# anemix.net
KiCad netlist of a schematic drawn in EAGLE
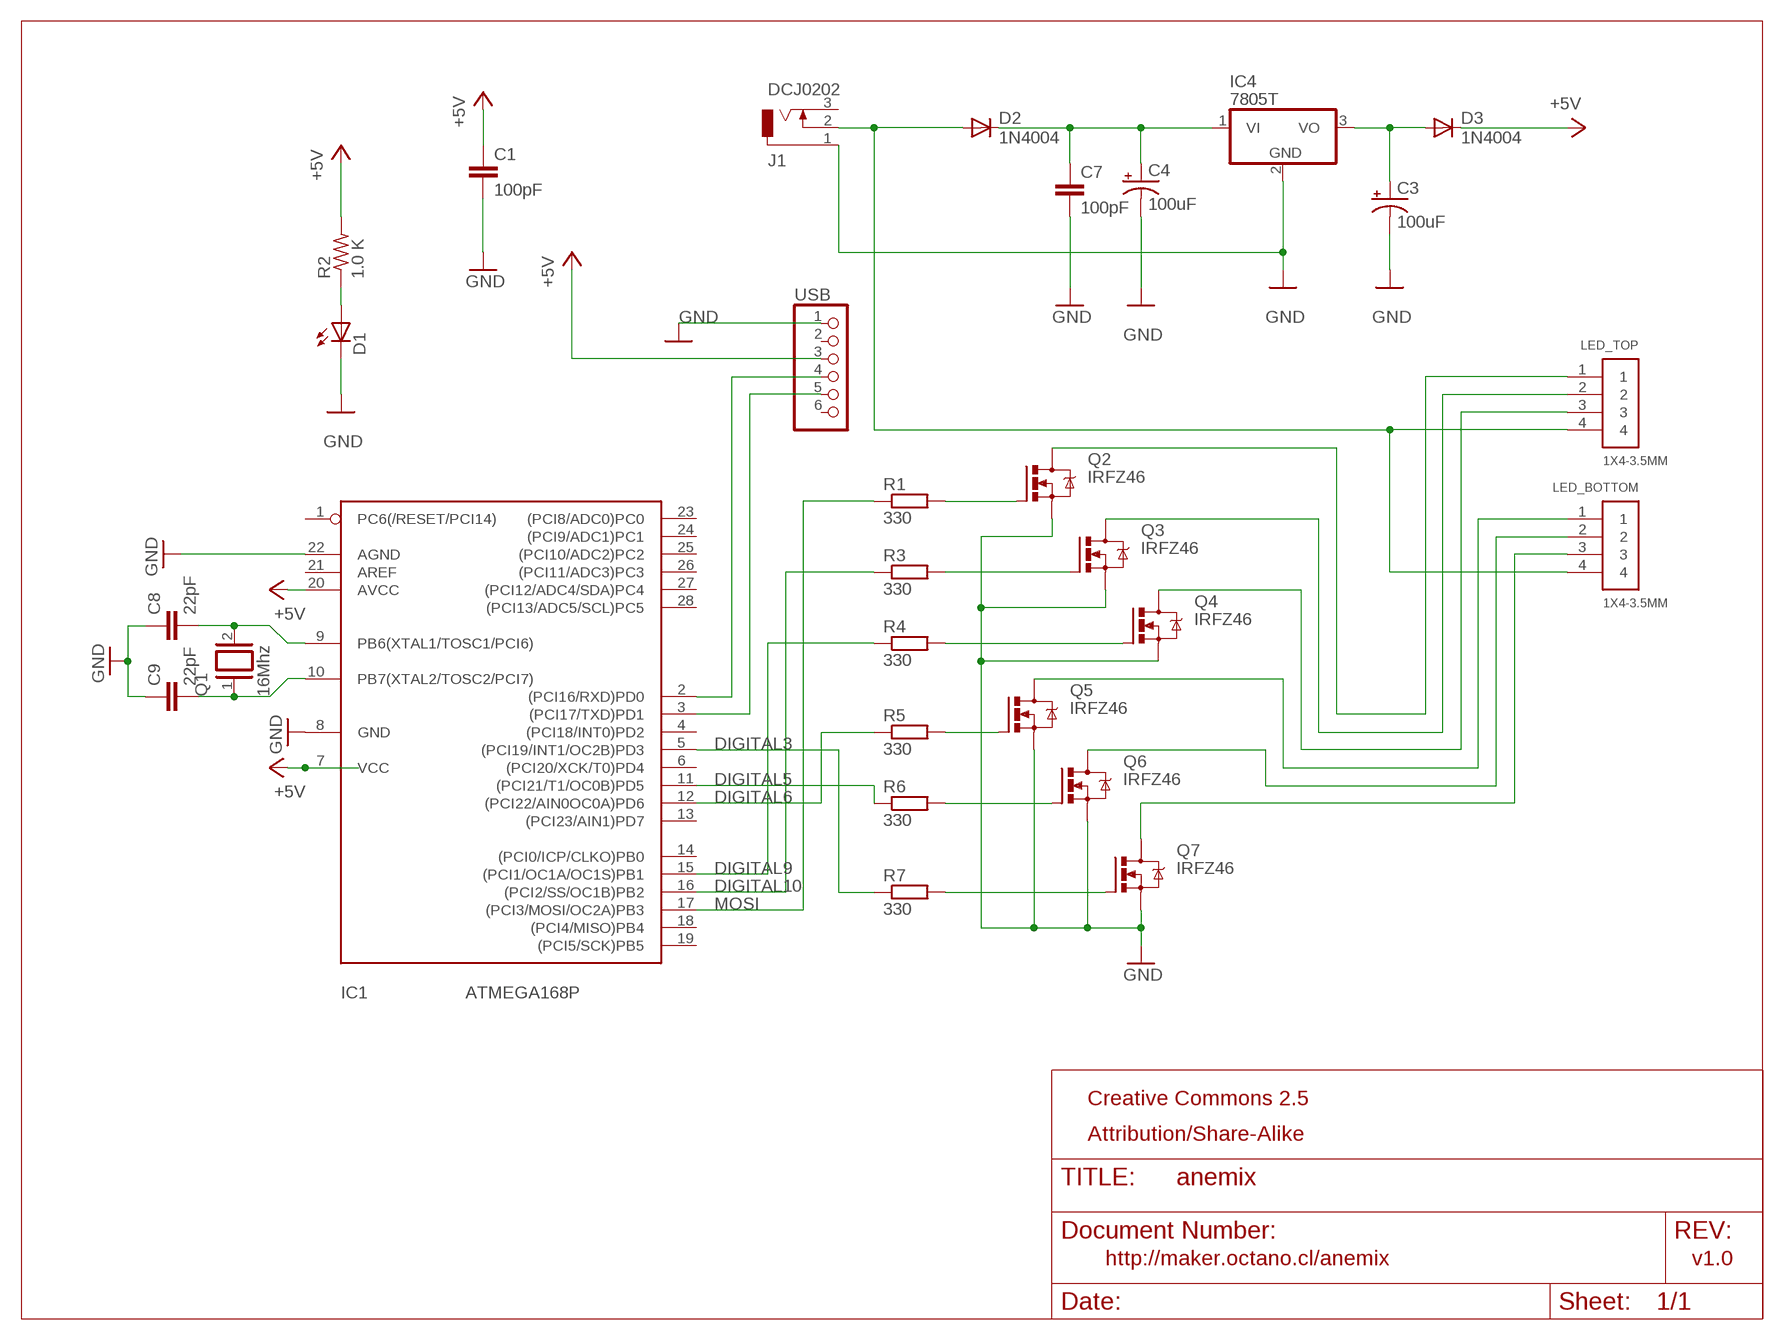
[diagram p0: schematic, sheet 1]

(export (version "E")
  (design (tool "Eeschema 10.0.6"))
  (components
    (comp (ref "C1")
      (value "100pF")
      (footprint "eagle-import:C025-025X050")
      (libsource (lib "eagle-import") (part "C-EU025-025X050"))
    )
    (comp (ref "C3")
      (value "100uF")
      (footprint "eagle-import:E2,5-7")
      (libsource (lib "eagle-import") (part "CPOL-USE2.5-7"))
    )
    (comp (ref "C4")
      (value "100uF")
      (footprint "eagle-import:E2,5-7")
      (libsource (lib "eagle-import") (part "CPOL-USE2.5-7"))
    )
    (comp (ref "C7")
      (value "100pF")
      (footprint "eagle-import:C025-025X050")
      (libsource (lib "eagle-import") (part "C-EU025-025X050"))
    )
    (comp (ref "C8")
      (value "22pF")
      (footprint "eagle-import:C025-025X050")
      (libsource (lib "eagle-import") (part "C-EU025-025X050"))
    )
    (comp (ref "C9")
      (value "22pF")
      (footprint "eagle-import:C025-025X050")
      (libsource (lib "eagle-import") (part "C-EU025-025X050"))
    )
    (comp (ref "D1")
      (value "LED3MM")
      (footprint "eagle-import:LED3MM")
      (libsource (lib "eagle-import") (part "LED3MM"))
    )
    (comp (ref "D2")
      (value "1N4004")
      (footprint "eagle-import:DO41-10")
      (libsource (lib "eagle-import") (part "1N4004"))
    )
    (comp (ref "D3")
      (value "1N4004")
      (footprint "eagle-import:DO41-10")
      (libsource (lib "eagle-import") (part "1N4004"))
    )
    (comp (ref "IC1")
      (value "ATMEGA168P")
      (footprint "eagle-import:DIL28_3")
      (libsource (lib "eagle-import") (part "ATMEGA168PROUND"))
    )
    (comp (ref "IC4")
      (value "7805T")
      (footprint "eagle-import:TO220H")
      (libsource (lib "eagle-import") (part "78T05"))
    )
    (comp (ref "J1")
      (value "DCJ0202")
      (footprint "eagle-import:DCJ0202")
      (libsource (lib "eagle-import") (part "DCJ0202"))
    )
    (comp (ref "LED_BOTTOM")
      (value "1X4-3.5MM")
      (footprint "eagle-import:1X04-3.5MM")
      (libsource (lib "eagle-import") (part "1X4-3.5MM"))
    )
    (comp (ref "LED_TOP")
      (value "1X4-3.5MM")
      (footprint "eagle-import:1X04-3.5MM")
      (libsource (lib "eagle-import") (part "1X4-3.5MM"))
    )
    (comp (ref "Q1")
      (value "16Mhz")
      (footprint "eagle-import:QS")
      (libsource (lib "eagle-import") (part "XTAL/S"))
    )
    (comp (ref "Q2")
      (value "IRFZ46")
      (footprint "eagle-import:TO220BH")
      (libsource (lib "eagle-import") (part "IRFZ48Z"))
    )
    (comp (ref "Q3")
      (value "IRFZ46")
      (footprint "eagle-import:TO220BH")
      (libsource (lib "eagle-import") (part "IRFZ48Z"))
    )
    (comp (ref "Q4")
      (value "IRFZ46")
      (footprint "eagle-import:TO220BH")
      (libsource (lib "eagle-import") (part "IRFZ48Z"))
    )
    (comp (ref "Q5")
      (value "IRFZ46")
      (footprint "eagle-import:TO220BH")
      (libsource (lib "eagle-import") (part "IRFZ48Z"))
    )
    (comp (ref "Q6")
      (value "IRFZ46")
      (footprint "eagle-import:TO220BH")
      (libsource (lib "eagle-import") (part "IRFZ48Z"))
    )
    (comp (ref "Q7")
      (value "IRFZ46")
      (footprint "eagle-import:TO220BH")
      (libsource (lib "eagle-import") (part "IRFZ48Z"))
    )
    (comp (ref "R1")
      (value "330")
      (footprint "eagle-import:0207_10")
      (libsource (lib "eagle-import") (part "R-EU_0207/10"))
    )
    (comp (ref "R2")
      (value "1.0 K")
      (footprint "eagle-import:0204_7")
      (libsource (lib "eagle-import") (part "R-US_0204/7"))
    )
    (comp (ref "R3")
      (value "330")
      (footprint "eagle-import:0207_10")
      (libsource (lib "eagle-import") (part "R-EU_0207/10"))
    )
    (comp (ref "R4")
      (value "330")
      (footprint "eagle-import:0207_10")
      (libsource (lib "eagle-import") (part "R-EU_0207/10"))
    )
    (comp (ref "R5")
      (value "330")
      (footprint "eagle-import:0207_10")
      (libsource (lib "eagle-import") (part "R-EU_0207/10"))
    )
    (comp (ref "R6")
      (value "330")
      (footprint "eagle-import:0207_10")
      (libsource (lib "eagle-import") (part "R-EU_0207/10"))
    )
    (comp (ref "R7")
      (value "330")
      (footprint "eagle-import:0207_10")
      (libsource (lib "eagle-import") (part "R-EU_0207/10"))
    )
    (comp (ref "USB")
      (value "PINHD-1X6")
      (footprint "eagle-import:1X06")
      (libsource (lib "eagle-import") (part "PINHD-1X6"))
    )
  )
  (nets
    (net (code "1") (name "+5V") (class "Default")
      (node (ref "C1") (pin "1") (pinfunction "1_1") (pintype "passive"))
      (node (ref "D3") (pin "C") (pinfunction "C_C") (pintype "passive"))
      (node (ref "IC1") (pin "20") (pinfunction "AVCC_20") (pintype "bidirectional"))
      (node (ref "IC1") (pin "7") (pinfunction "VCC_7") (pintype "bidirectional"))
      (node (ref "R2") (pin "2") (pinfunction "2_2") (pintype "passive"))
      (node (ref "USB") (pin "3") (pinfunction "3_3") (pintype "passive"))
    )
    (net (code "2") (name "/DIGITAL3") (class "Default")
      (node (ref "IC1") (pin "5") (pinfunction "(PCI19/INT1/OC2B)PD3_5") (pintype "bidirectional"))
      (node (ref "R7") (pin "1") (pinfunction "1_1") (pintype "passive"))
    )
    (net (code "3") (name "/DIGITAL5") (class "Default")
      (node (ref "IC1") (pin "11") (pinfunction "(PCI21/T1/OC0B)PD5_11") (pintype "bidirectional"))
      (node (ref "R6") (pin "1") (pinfunction "1_1") (pintype "passive"))
    )
    (net (code "4") (name "/DIGITAL6") (class "Default")
      (node (ref "IC1") (pin "12") (pinfunction "(PCI22/AIN0OC0A)PD6_12") (pintype "bidirectional"))
      (node (ref "R5") (pin "1") (pinfunction "1_1") (pintype "passive"))
    )
    (net (code "5") (name "/DIGITAL9") (class "Default")
      (node (ref "IC1") (pin "15") (pinfunction "(PCI1/OC1A/OC1S)PB1_15") (pintype "bidirectional"))
      (node (ref "R4") (pin "1") (pinfunction "1_1") (pintype "passive"))
    )
    (net (code "6") (name "/DIGITAL10") (class "Default")
      (node (ref "IC1") (pin "16") (pinfunction "(PCI2/SS/OC1B)PB2_16") (pintype "bidirectional"))
      (node (ref "R3") (pin "1") (pinfunction "1_1") (pintype "passive"))
    )
    (net (code "7") (name "/MOSI") (class "Default")
      (node (ref "IC1") (pin "17") (pinfunction "(PCI3/MOSI/OC2A)PB3_17") (pintype "bidirectional"))
      (node (ref "R1") (pin "1") (pinfunction "1_1") (pintype "passive"))
    )
    (net (code "8") (name "GND") (class "Default")
      (node (ref "C1") (pin "2") (pinfunction "2_2") (pintype "passive"))
      (node (ref "C3") (pin "-") (pinfunction "-_-") (pintype "passive"))
      (node (ref "C4") (pin "-") (pinfunction "-_-") (pintype "passive"))
      (node (ref "C7") (pin "2") (pinfunction "2_2") (pintype "passive"))
      (node (ref "C8") (pin "1") (pinfunction "1_1") (pintype "passive"))
      (node (ref "C9") (pin "1") (pinfunction "1_1") (pintype "passive"))
      (node (ref "D1") (pin "K") (pinfunction "C_K") (pintype "passive"))
      (node (ref "IC1") (pin "22") (pinfunction "AGND_22") (pintype "bidirectional"))
      (node (ref "IC1") (pin "8") (pinfunction "GND_8") (pintype "bidirectional"))
      (node (ref "IC4") (pin "2") (pinfunction "GND_2") (pintype "passive"))
      (node (ref "J1") (pin "1") (pinfunction "1_1") (pintype "passive"))
      (node (ref "Q2") (pin "S") (pinfunction "S_S") (pintype "passive"))
      (node (ref "Q3") (pin "S") (pinfunction "S_S") (pintype "passive"))
      (node (ref "Q4") (pin "S") (pinfunction "S_S") (pintype "passive"))
      (node (ref "Q5") (pin "S") (pinfunction "S_S") (pintype "passive"))
      (node (ref "Q6") (pin "S") (pinfunction "S_S") (pintype "passive"))
      (node (ref "Q7") (pin "S") (pinfunction "S_S") (pintype "passive"))
      (node (ref "USB") (pin "1") (pinfunction "1_1") (pintype "passive"))
    )
    (net (code "9") (name "Net-(D1-PadA)") (class "Default")
      (node (ref "D1") (pin "A") (pinfunction "A_A") (pintype "passive"))
      (node (ref "R2") (pin "1") (pinfunction "1_1") (pintype "passive"))
    )
    (net (code "10") (name "Net-(D2-PadA)") (class "Default")
      (node (ref "D2") (pin "A") (pinfunction "A_A") (pintype "passive"))
      (node (ref "J1") (pin "2") (pinfunction "2_2") (pintype "passive"))
      (node (ref "LED_BOTTOM") (pin "4") (pinfunction "4_4") (pintype "bidirectional"))
      (node (ref "LED_TOP") (pin "4") (pinfunction "4_4") (pintype "bidirectional"))
    )
    (net (code "11") (name "Net-(IC1-(PCI16{slash}RXD)PD0)") (class "Default")
      (node (ref "IC1") (pin "2") (pinfunction "(PCI16/RXD)PD0_2") (pintype "bidirectional"))
      (node (ref "USB") (pin "4") (pinfunction "4_4") (pintype "passive"))
    )
    (net (code "12") (name "Net-(IC1-(PCI17{slash}TXD)PD1)") (class "Default")
      (node (ref "IC1") (pin "3") (pinfunction "(PCI17/TXD)PD1_3") (pintype "bidirectional"))
      (node (ref "USB") (pin "5") (pinfunction "5_5") (pintype "passive"))
    )
    (net (code "13") (name "Net-(IC1-PB6(XTAL1{slash}TOSC1{slash}PCI6))") (class "Default")
      (node (ref "C8") (pin "2") (pinfunction "2_2") (pintype "passive"))
      (node (ref "IC1") (pin "9") (pinfunction "PB6(XTAL1/TOSC1/PCI6)_9") (pintype "bidirectional"))
      (node (ref "Q1") (pin "2") (pinfunction "2_2") (pintype "passive"))
    )
    (net (code "14") (name "Net-(IC1-PB7(XTAL2{slash}TOSC2{slash}PCI7))") (class "Default")
      (node (ref "C9") (pin "2") (pinfunction "2_2") (pintype "passive"))
      (node (ref "IC1") (pin "10") (pinfunction "PB7(XTAL2/TOSC2/PCI7)_10") (pintype "bidirectional"))
      (node (ref "Q1") (pin "1") (pinfunction "1_1") (pintype "passive"))
    )
    (net (code "15") (name "Net-(IC4-VI)") (class "Default")
      (node (ref "C4") (pin "+") (pinfunction "+_+") (pintype "passive"))
      (node (ref "C7") (pin "1") (pinfunction "1_1") (pintype "passive"))
      (node (ref "D2") (pin "C") (pinfunction "C_C") (pintype "passive"))
      (node (ref "IC4") (pin "1") (pinfunction "VI_1") (pintype "input"))
    )
    (net (code "16") (name "Net-(IC4-VO)") (class "Default")
      (node (ref "C3") (pin "+") (pinfunction "+_+") (pintype "passive"))
      (node (ref "D3") (pin "A") (pinfunction "A_A") (pintype "passive"))
      (node (ref "IC4") (pin "3") (pinfunction "VO_3") (pintype "passive"))
    )
    (net (code "17") (name "Net-(LED_BOTTOM-Pad1)") (class "Default")
      (node (ref "LED_BOTTOM") (pin "1") (pinfunction "1_1") (pintype "bidirectional"))
      (node (ref "Q5") (pin "D") (pinfunction "D_D") (pintype "passive"))
    )
    (net (code "18") (name "Net-(LED_BOTTOM-Pad2)") (class "Default")
      (node (ref "LED_BOTTOM") (pin "2") (pinfunction "2_2") (pintype "bidirectional"))
      (node (ref "Q6") (pin "D") (pinfunction "D_D") (pintype "passive"))
    )
    (net (code "19") (name "Net-(LED_BOTTOM-Pad3)") (class "Default")
      (node (ref "LED_BOTTOM") (pin "3") (pinfunction "3_3") (pintype "bidirectional"))
      (node (ref "Q7") (pin "D") (pinfunction "D_D") (pintype "passive"))
    )
    (net (code "20") (name "Net-(LED_TOP-Pad1)") (class "Default")
      (node (ref "LED_TOP") (pin "1") (pinfunction "1_1") (pintype "bidirectional"))
      (node (ref "Q2") (pin "D") (pinfunction "D_D") (pintype "passive"))
    )
    (net (code "21") (name "Net-(LED_TOP-Pad2)") (class "Default")
      (node (ref "LED_TOP") (pin "2") (pinfunction "2_2") (pintype "bidirectional"))
      (node (ref "Q3") (pin "D") (pinfunction "D_D") (pintype "passive"))
    )
    (net (code "22") (name "Net-(LED_TOP-Pad3)") (class "Default")
      (node (ref "LED_TOP") (pin "3") (pinfunction "3_3") (pintype "bidirectional"))
      (node (ref "Q4") (pin "D") (pinfunction "D_D") (pintype "passive"))
    )
    (net (code "23") (name "Net-(Q2-PadG)") (class "Default")
      (node (ref "Q2") (pin "G") (pinfunction "G_G") (pintype "passive"))
      (node (ref "R1") (pin "2") (pinfunction "2_2") (pintype "passive"))
    )
    (net (code "24") (name "Net-(Q3-PadG)") (class "Default")
      (node (ref "Q3") (pin "G") (pinfunction "G_G") (pintype "passive"))
      (node (ref "R3") (pin "2") (pinfunction "2_2") (pintype "passive"))
    )
    (net (code "25") (name "Net-(Q4-PadG)") (class "Default")
      (node (ref "Q4") (pin "G") (pinfunction "G_G") (pintype "passive"))
      (node (ref "R4") (pin "2") (pinfunction "2_2") (pintype "passive"))
    )
    (net (code "26") (name "Net-(Q5-PadG)") (class "Default")
      (node (ref "Q5") (pin "G") (pinfunction "G_G") (pintype "passive"))
      (node (ref "R5") (pin "2") (pinfunction "2_2") (pintype "passive"))
    )
    (net (code "27") (name "Net-(Q6-PadG)") (class "Default")
      (node (ref "Q6") (pin "G") (pinfunction "G_G") (pintype "passive"))
      (node (ref "R6") (pin "2") (pinfunction "2_2") (pintype "passive"))
    )
    (net (code "28") (name "Net-(Q7-PadG)") (class "Default")
      (node (ref "Q7") (pin "G") (pinfunction "G_G") (pintype "passive"))
      (node (ref "R7") (pin "2") (pinfunction "2_2") (pintype "passive"))
    )
    (net (code "29") (name "unconnected-(IC1-(PCI0{slash}ICP{slash}CLKO)PB0-Pad14)") (class "Default")
      (node (ref "IC1") (pin "14") (pinfunction "(PCI0/ICP/CLKO)PB0_14") (pintype "bidirectional"))
    )
    (net (code "30") (name "unconnected-(IC1-(PCI4{slash}MISO)PB4-Pad18)") (class "Default")
      (node (ref "IC1") (pin "18") (pinfunction "(PCI4/MISO)PB4_18") (pintype "bidirectional"))
    )
    (net (code "31") (name "unconnected-(IC1-(PCI5{slash}SCK)PB5-Pad19)") (class "Default")
      (node (ref "IC1") (pin "19") (pinfunction "(PCI5/SCK)PB5_19") (pintype "bidirectional"))
    )
    (net (code "32") (name "unconnected-(IC1-(PCI8{slash}ADC0)PC0-Pad23)") (class "Default")
      (node (ref "IC1") (pin "23") (pinfunction "(PCI8/ADC0)PC0_23") (pintype "bidirectional"))
    )
    (net (code "33") (name "unconnected-(IC1-(PCI9{slash}ADC1)PC1-Pad24)") (class "Default")
      (node (ref "IC1") (pin "24") (pinfunction "(PCI9/ADC1)PC1_24") (pintype "bidirectional"))
    )
    (net (code "34") (name "unconnected-(IC1-(PCI10{slash}ADC2)PC2-Pad25)") (class "Default")
      (node (ref "IC1") (pin "25") (pinfunction "(PCI10/ADC2)PC2_25") (pintype "bidirectional"))
    )
    (net (code "35") (name "unconnected-(IC1-(PCI11{slash}ADC3)PC3-Pad26)") (class "Default")
      (node (ref "IC1") (pin "26") (pinfunction "(PCI11/ADC3)PC3_26") (pintype "bidirectional"))
    )
    (net (code "36") (name "unconnected-(IC1-(PCI12{slash}ADC4{slash}SDA)PC4-Pad27)") (class "Default")
      (node (ref "IC1") (pin "27") (pinfunction "(PCI12/ADC4/SDA)PC4_27") (pintype "bidirectional"))
    )
    (net (code "37") (name "unconnected-(IC1-(PCI13{slash}ADC5{slash}SCL)PC5-Pad28)") (class "Default")
      (node (ref "IC1") (pin "28") (pinfunction "(PCI13/ADC5/SCL)PC5_28") (pintype "bidirectional"))
    )
    (net (code "38") (name "unconnected-(IC1-(PCI18{slash}INT0)PD2-Pad4)") (class "Default")
      (node (ref "IC1") (pin "4") (pinfunction "(PCI18/INT0)PD2_4") (pintype "bidirectional"))
    )
    (net (code "39") (name "unconnected-(IC1-(PCI20{slash}XCK{slash}T0)PD4-Pad6)") (class "Default")
      (node (ref "IC1") (pin "6") (pinfunction "(PCI20/XCK/T0)PD4_6") (pintype "bidirectional"))
    )
    (net (code "40") (name "unconnected-(IC1-(PCI23{slash}AIN1)PD7-Pad13)") (class "Default")
      (node (ref "IC1") (pin "13") (pinfunction "(PCI23/AIN1)PD7_13") (pintype "bidirectional"))
    )
    (net (code "41") (name "unconnected-(IC1-AREF-Pad21)") (class "Default")
      (node (ref "IC1") (pin "21") (pinfunction "AREF_21") (pintype "bidirectional"))
    )
    (net (code "42") (name "unconnected-(IC1-PC6({slash}RESET{slash}PCI14)-Pad1)") (class "Default")
      (node (ref "IC1") (pin "1") (pinfunction "PC6(/RESET/PCI14)_1") (pintype "bidirectional"))
    )
    (net (code "43") (name "unconnected-(J1-Pad3)") (class "Default")
      (node (ref "J1") (pin "3") (pinfunction "3_3") (pintype "passive"))
    )
    (net (code "44") (name "unconnected-(USB-Pad2)") (class "Default")
      (node (ref "USB") (pin "2") (pinfunction "2_2") (pintype "passive"))
    )
    (net (code "45") (name "unconnected-(USB-Pad6)") (class "Default")
      (node (ref "USB") (pin "6") (pinfunction "6_6") (pintype "passive"))
    )
  )
)
